# Fri3D_2020_Power.net
KiCad netlist of a schematic drawn in Altium Designer
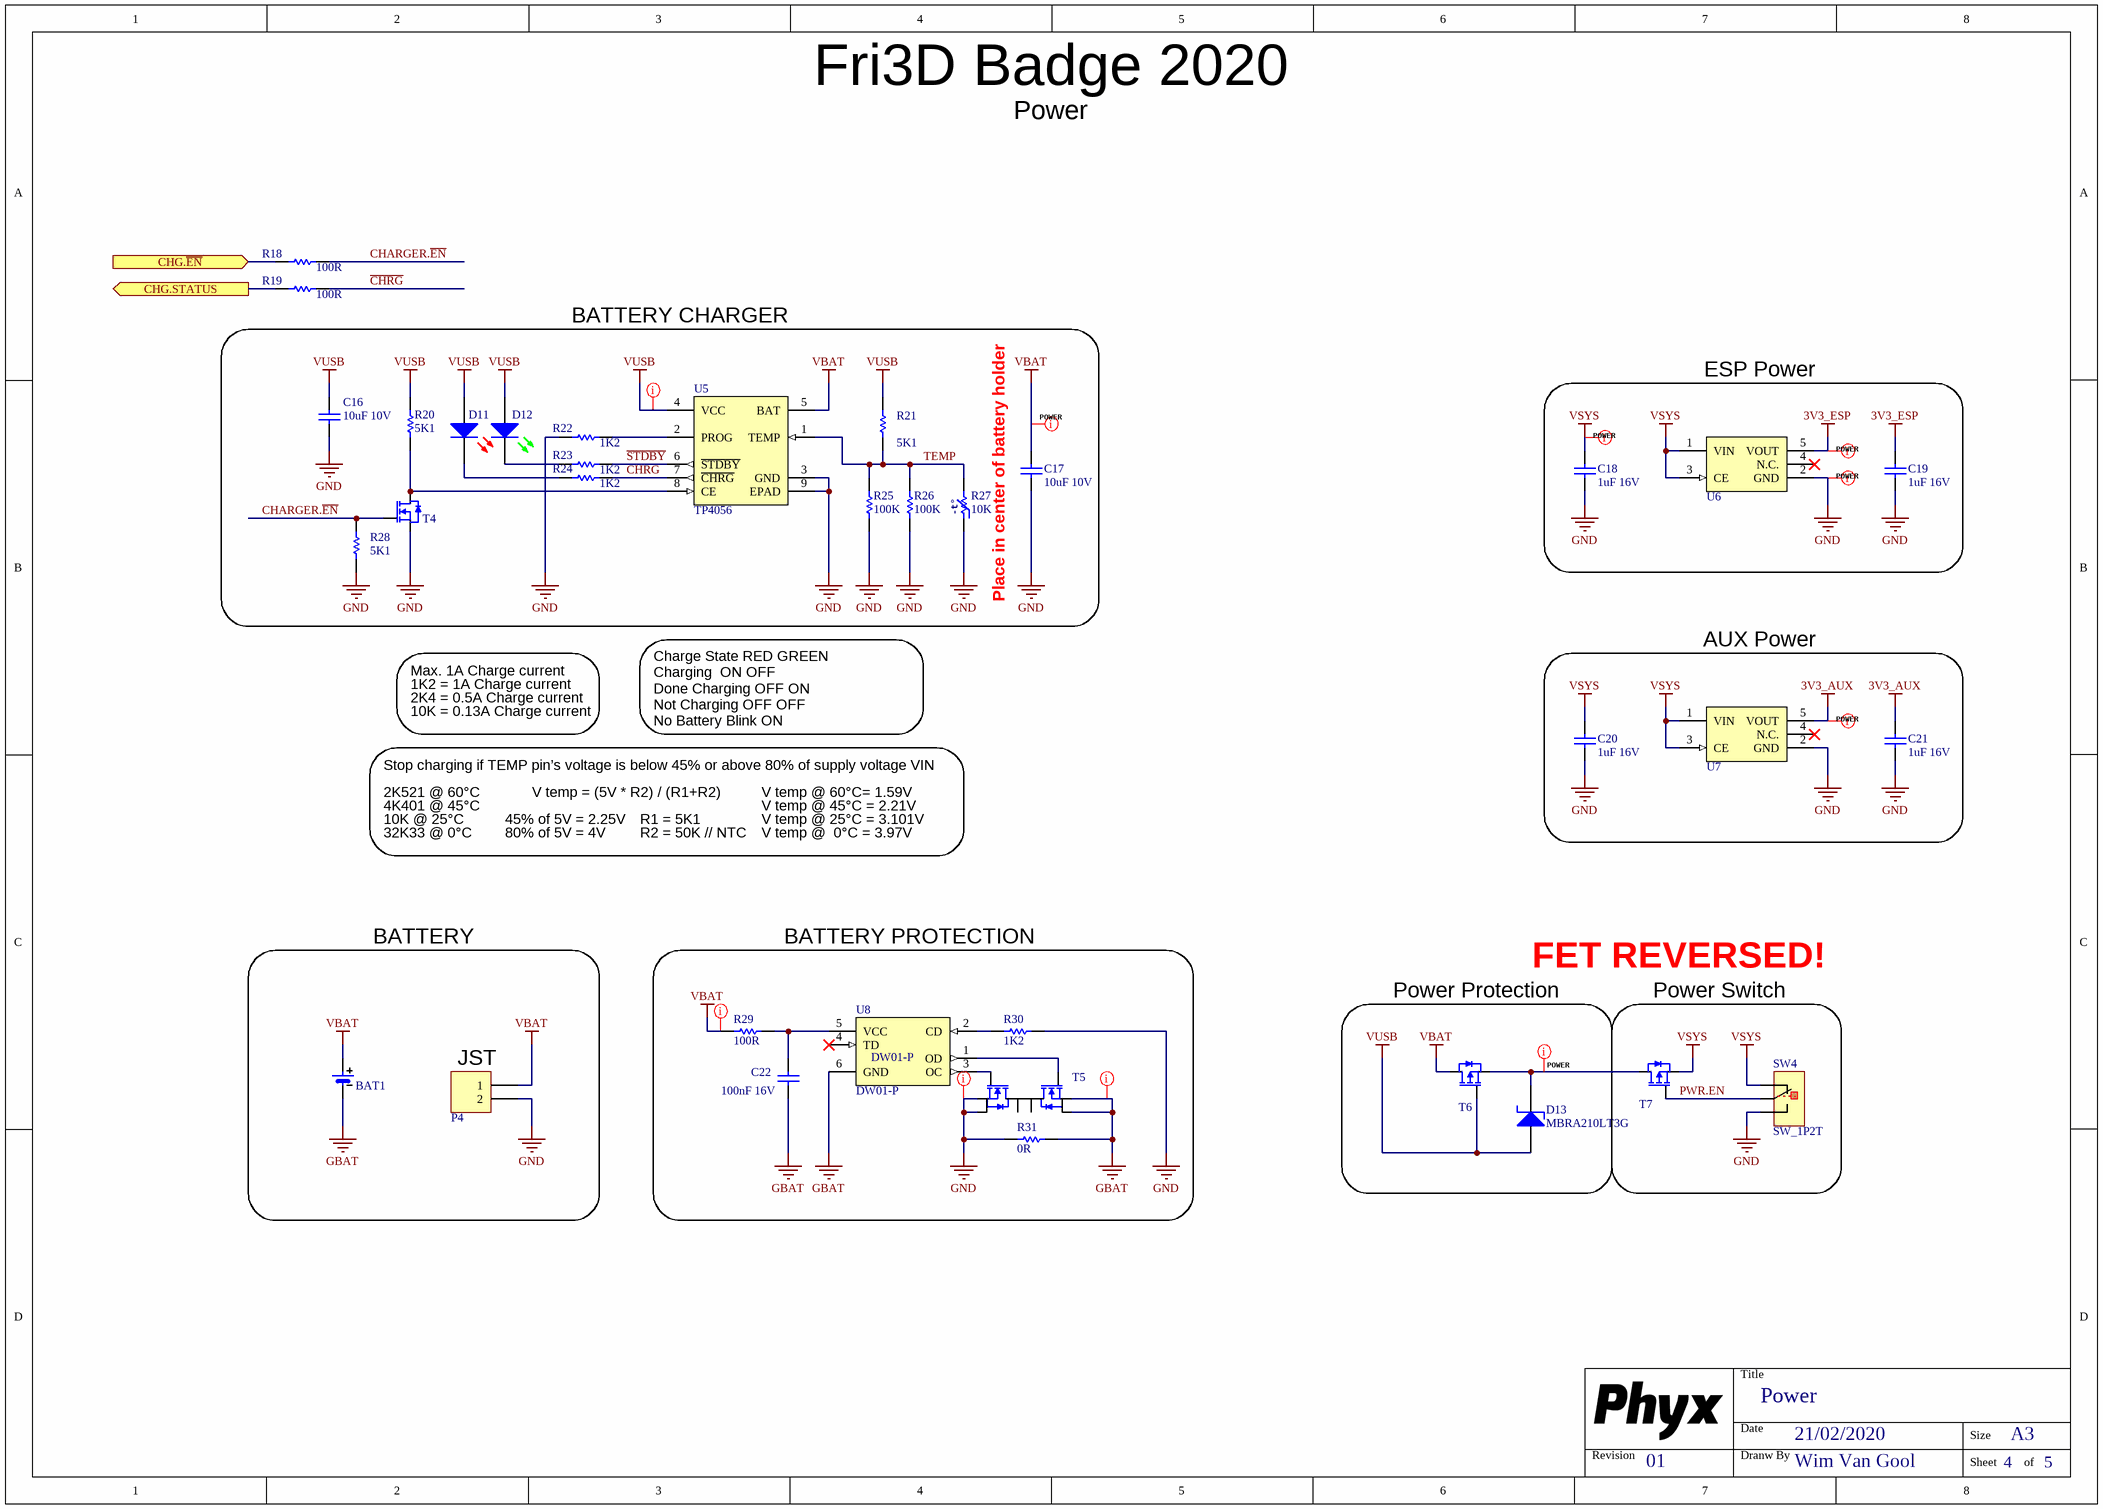
[diagram p0: Fri3D_2020_Power.SchDoc]

(export (version "E")
  (design (tool "Eeschema 10.0.6"))
  (components
    (comp (ref "BAT1")
      (value "18650 Battery holder with spring")
      (footprint "BAT_18650_SPRING")
      (description "=Description")
      (libsource (lib "Phyx_Components") (part "BAT_2"))
    )
    (comp (ref "C16")
      (value "10uF 10V")
      (footprint "C0805_N")
      (description "Capacitor Ceramic")
      (fields (field (name "Comment") "CAP_CERAMIC"))
      (libsource (lib "Phyx_Components") (part "CAP_CERAMIC"))
    )
    (comp (ref "C17")
      (value "10uF 10V")
      (footprint "C0805_N")
      (description "Capacitor Ceramic")
      (fields (field (name "Comment") "CAP_CERAMIC"))
      (libsource (lib "Phyx_Components") (part "CAP_CERAMIC"))
    )
    (comp (ref "C18")
      (value "1uF 16V")
      (footprint "C0603_N")
      (description "Capacitor Ceramic")
      (fields (field (name "Comment") "CAP_CERAMIC"))
      (libsource (lib "Phyx_Components") (part "CAP_CERAMIC"))
    )
    (comp (ref "C19")
      (value "1uF 16V")
      (footprint "C0603_N")
      (description "Capacitor Ceramic")
      (fields (field (name "Comment") "CAP_CERAMIC"))
      (libsource (lib "Phyx_Components") (part "CAP_CERAMIC"))
    )
    (comp (ref "C20")
      (value "1uF 16V")
      (footprint "C0603_N")
      (description "Capacitor Ceramic")
      (fields (field (name "Comment") "CAP_CERAMIC"))
      (libsource (lib "Phyx_Components") (part "CAP_CERAMIC"))
    )
    (comp (ref "C21")
      (value "1uF 16V")
      (footprint "C0603_N")
      (description "Capacitor Ceramic")
      (fields (field (name "Comment") "CAP_CERAMIC"))
      (libsource (lib "Phyx_Components") (part "CAP_CERAMIC"))
    )
    (comp (ref "C22")
      (value "100nF 16V")
      (footprint "C0603_N")
      (description "Capacitor Ceramic")
      (libsource (lib "Phyx_Components") (part "CAP_CERAMIC"))
    )
    (comp (ref "D11")
      (value "Default 0805 Red LED")
      (footprint "LED_0805_RD")
      (description "=Description")
      (libsource (lib "Phyx_Components") (part "LED_RED"))
    )
    (comp (ref "D12")
      (value "Default 0805 Green LED")
      (footprint "LED_0805_GR")
      (description "=Description")
      (libsource (lib "Phyx_Components") (part "LED_GREEN"))
    )
    (comp (ref "D13")
      (value "MBRA210LT3G")
      (footprint "SMA_AC")
      (description "=Description")
      (libsource (lib "Phyx_Components") (part "Schottky_AC"))
    )
    (comp (ref "P4")
      (value "Header 2.0mm Shrouded 2")
      (footprint "WE_620102131822")
      (libsource (lib "Phyx_Components") (part "Header 2"))
    )
    (comp (ref "R18")
      (value "100R")
      (footprint "R0603_N")
      (fields (field (name "Comment") "RESISTOR"))
      (libsource (lib "Phyx_Components") (part "RESISTOR"))
    )
    (comp (ref "R19")
      (value "100R")
      (footprint "R0603_N")
      (fields (field (name "Comment") "RESISTOR"))
      (libsource (lib "Phyx_Components") (part "RESISTOR"))
    )
    (comp (ref "R20")
      (value "5K1")
      (footprint "R0603_N")
      (fields (field (name "Comment") "RESISTOR"))
      (libsource (lib "Phyx_Components") (part "RESISTOR"))
    )
    (comp (ref "R21")
      (value "5K1")
      (footprint "R0603_N")
      (fields (field (name "Comment") "RESISTOR"))
      (libsource (lib "Phyx_Components") (part "RESISTOR"))
    )
    (comp (ref "R22")
      (value "1K2")
      (footprint "R0603_N")
      (fields (field (name "Comment") "RESISTOR"))
      (libsource (lib "Phyx_Components") (part "RESISTOR"))
    )
    (comp (ref "R23")
      (value "1K2")
      (footprint "R0603_N")
      (fields (field (name "Comment") "RESISTOR"))
      (libsource (lib "Phyx_Components") (part "RESISTOR"))
    )
    (comp (ref "R24")
      (value "1K2")
      (footprint "R0603_N")
      (fields (field (name "Comment") "RESISTOR"))
      (libsource (lib "Phyx_Components") (part "RESISTOR"))
    )
    (comp (ref "R25")
      (value "100K")
      (footprint "R0603_N")
      (fields (field (name "Comment") "RESISTOR"))
      (libsource (lib "Phyx_Components") (part "RESISTOR"))
    )
    (comp (ref "R26")
      (value "100K")
      (footprint "R0603_N")
      (fields (field (name "Comment") "RESISTOR"))
      (libsource (lib "Phyx_Components") (part "RESISTOR"))
    )
    (comp (ref "R27")
      (value "10K")
      (footprint "R0402")
      (fields (field (name "Comment") "NTC"))
      (libsource (lib "Phyx_Components") (part "RESISTOR_NTC"))
    )
    (comp (ref "R28")
      (value "5K1")
      (footprint "R0603_N")
      (fields (field (name "Comment") "RESISTOR"))
      (libsource (lib "Phyx_Components") (part "RESISTOR"))
    )
    (comp (ref "R29")
      (value "100R")
      (footprint "R0603_N")
      (fields (field (name "Comment") "RESISTOR"))
      (libsource (lib "Phyx_Components") (part "RESISTOR"))
    )
    (comp (ref "R30")
      (value "1K2")
      (footprint "R0603_N")
      (fields (field (name "Comment") "RESISTOR"))
      (libsource (lib "Phyx_Components") (part "RESISTOR"))
    )
    (comp (ref "R31")
      (value "0R")
      (footprint "R0603_N")
      (libsource (lib "Phyx_Components") (part "RESISTOR"))
    )
    (comp (ref "SW4")
      (value "SW_1P2T")
      (footprint "WE_450404015514")
      (libsource (lib "Phyx_Components") (part "SW_1P2T"))
    )
    (comp (ref "T4")
      (value "0.2A N-Ch MOSFET Vgs 3.2")
      (footprint "SOT23-3")
      (libsource (lib "Phyx_Components") (part "N_MOSFET_GSD"))
    )
    (comp (ref "T5")
      (value "Dual N-Ch MOSFET Common Drain")
      (footprint "TSSOP_8_65P")
      (description "=Description")
      (libsource (lib "Phyx_Components") (part "N_MOSFET_FS8205A"))
    )
    (comp (ref "T6")
      (value "-2.3A -20V P-Ch MOSFET Vgs -1V")
      (footprint "SOT23-3")
      (description "=Description")
      (libsource (lib "Phyx_Components") (part "P_MOSFET_GSD"))
    )
    (comp (ref "T7")
      (value "-2.3A -20V P-Ch MOSFET Vgs -1V")
      (footprint "SOT23-3")
      (description "=Description")
      (libsource (lib "Phyx_Components") (part "P_MOSFET_GSD"))
    )
    (comp (ref "U5")
      (value "TP4056")
      (footprint "SOIC_N_8_TH")
      (description "=Description")
      (fields (field (name "Comment") "Single Cell LiIon charger max 1A"))
      (libsource (lib "Phyx_Components") (part "TP4056"))
    )
    (comp (ref "U6")
      (value "3V3 LDO 700mA 50mV")
      (footprint "SOT23-5")
      (description "=Designator")
      (libsource (lib "Phyx_Components") (part "XC6210_SOT"))
    )
    (comp (ref "U7")
      (value "3V3 LDO 700mA 50mV")
      (footprint "SOT23-5")
      (description "=Designator")
      (libsource (lib "Phyx_Components") (part "XC6210_SOT"))
    )
    (comp (ref "U8")
      (value "DW01-P")
      (footprint "SOT23-6")
      (description "=Description")
      (fields (field (name "Comment") "DW01-P single cell lithium protection"))
      (libsource (lib "Phyx_Components") (part "DW01-P"))
    )
  )
  (nets
    (net (code "1") (name "/CHARGER.~{EN}") (class "Default")
      (node (ref "R18") (pin "2") (pinfunction "2_2") (pintype "passive"))
      (node (ref "R28") (pin "1") (pinfunction "1_1") (pintype "passive"))
      (node (ref "T4") (pin "1") (pinfunction "G_1") (pintype "passive"))
    )
    (net (code "2") (name "/CHG.STATUS") (class "Default")
      (node (ref "R19") (pin "1") (pinfunction "1_1") (pintype "passive"))
    )
    (net (code "3") (name "/CHG.~{EN}") (class "Default")
      (node (ref "R18") (pin "1") (pinfunction "1_1") (pintype "passive"))
    )
    (net (code "4") (name "/PWR.EN") (class "Default")
      (node (ref "SW4") (pin "2") (pinfunction "2_2") (pintype "passive"))
      (node (ref "T7") (pin "1") (pinfunction "G_1") (pintype "passive"))
    )
    (net (code "5") (name "/TEMP") (class "Default")
      (node (ref "R21") (pin "2") (pinfunction "2_2") (pintype "passive"))
      (node (ref "R25") (pin "1") (pinfunction "1_1") (pintype "passive"))
      (node (ref "R26") (pin "1") (pinfunction "1_1") (pintype "passive"))
      (node (ref "R27") (pin "1") (pinfunction "1_1") (pintype "passive"))
      (node (ref "U5") (pin "1") (pinfunction "TEMP_1") (pintype "input"))
    )
    (net (code "6") (name "/~{CHRG}") (class "Default")
      (node (ref "R19") (pin "2") (pinfunction "2_2") (pintype "passive"))
      (node (ref "R24") (pin "2") (pinfunction "2_2") (pintype "passive"))
      (node (ref "U5") (pin "7") (pinfunction "~{CHRG}_7") (pintype "output"))
    )
    (net (code "7") (name "/~{STDBY}") (class "Default")
      (node (ref "R23") (pin "2") (pinfunction "2_2") (pintype "passive"))
      (node (ref "U5") (pin "6") (pinfunction "~{STDBY}_6") (pintype "output"))
    )
    (net (code "8") (name "3V3_AUX") (class "Default")
      (node (ref "C21") (pin "1") (pinfunction "1_1") (pintype "passive"))
      (node (ref "U7") (pin "5") (pinfunction "VOUT_5") (pintype "power_in"))
    )
    (net (code "9") (name "3V3_ESP") (class "Default")
      (node (ref "C19") (pin "1") (pinfunction "1_1") (pintype "passive"))
      (node (ref "U6") (pin "5") (pinfunction "VOUT_5") (pintype "power_in"))
    )
    (net (code "10") (name "GBAT") (class "Default")
      (node (ref "BAT1") (pin "2") (pinfunction "2_2") (pintype "passive"))
      (node (ref "C22") (pin "2") (pinfunction "2_2") (pintype "passive"))
      (node (ref "R31") (pin "1") (pinfunction "1_1") (pintype "passive"))
      (node (ref "T5") (pin "2") (pinfunction "S1_2") (pintype "passive"))
      (node (ref "T5") (pin "3") (pinfunction "S1_3") (pintype "passive"))
      (node (ref "U8") (pin "6") (pinfunction "GND_6") (pintype "power_in"))
    )
    (net (code "11") (name "GND") (class "Default")
      (node (ref "C16") (pin "2") (pinfunction "2_2") (pintype "passive"))
      (node (ref "C17") (pin "2") (pinfunction "2_2") (pintype "passive"))
      (node (ref "C18") (pin "2") (pinfunction "2_2") (pintype "passive"))
      (node (ref "C19") (pin "2") (pinfunction "2_2") (pintype "passive"))
      (node (ref "C20") (pin "2") (pinfunction "2_2") (pintype "passive"))
      (node (ref "C21") (pin "2") (pinfunction "2_2") (pintype "passive"))
      (node (ref "P4") (pin "2") (pinfunction "2_2") (pintype "passive"))
      (node (ref "R22") (pin "2") (pinfunction "2_2") (pintype "passive"))
      (node (ref "R25") (pin "2") (pinfunction "2_2") (pintype "passive"))
      (node (ref "R26") (pin "2") (pinfunction "2_2") (pintype "passive"))
      (node (ref "R27") (pin "2") (pinfunction "2_2") (pintype "passive"))
      (node (ref "R28") (pin "2") (pinfunction "2_2") (pintype "passive"))
      (node (ref "R30") (pin "2") (pinfunction "2_2") (pintype "passive"))
      (node (ref "R31") (pin "2") (pinfunction "2_2") (pintype "passive"))
      (node (ref "SW4") (pin "3") (pinfunction "3_3") (pintype "passive"))
      (node (ref "T4") (pin "2") (pinfunction "S_2") (pintype "passive"))
      (node (ref "T5") (pin "6") (pinfunction "S2_6") (pintype "passive"))
      (node (ref "T5") (pin "7") (pinfunction "S2_7") (pintype "passive"))
      (node (ref "U5") (pin "3") (pinfunction "GND_3") (pintype "power_in"))
      (node (ref "U5") (pin "9") (pinfunction "EPAD_9") (pintype "power_in"))
      (node (ref "U6") (pin "2") (pinfunction "GND_2") (pintype "power_in"))
      (node (ref "U7") (pin "2") (pinfunction "GND_2") (pintype "power_in"))
    )
    (net (code "12") (name "Net-(D11-K)") (class "Default")
      (node (ref "D11") (pin "2") (pinfunction "K_2") (pintype "passive"))
      (node (ref "R24") (pin "1") (pinfunction "1_1") (pintype "passive"))
    )
    (net (code "13") (name "Net-(D12-K)") (class "Default")
      (node (ref "D12") (pin "2") (pinfunction "K_2") (pintype "passive"))
      (node (ref "R23") (pin "1") (pinfunction "1_1") (pintype "passive"))
    )
    (net (code "14") (name "Net-(T4-D)") (class "Default")
      (node (ref "R20") (pin "2") (pinfunction "2_2") (pintype "passive"))
      (node (ref "T4") (pin "3") (pinfunction "D_3") (pintype "passive"))
      (node (ref "U5") (pin "8") (pinfunction "CE_8") (pintype "input"))
    )
    (net (code "15") (name "Net-(T5-G1)") (class "Default")
      (node (ref "T5") (pin "4") (pinfunction "G1_4") (pintype "passive"))
      (node (ref "U8") (pin "1") (pinfunction "OD_1") (pintype "output"))
    )
    (net (code "16") (name "Net-(T5-G2)") (class "Default")
      (node (ref "T5") (pin "5") (pinfunction "G2_5") (pintype "passive"))
      (node (ref "U8") (pin "3") (pinfunction "OC_3") (pintype "output"))
    )
    (net (code "17") (name "Net-(T6-S)") (class "Default")
      (node (ref "D13") (pin "C") (pinfunction "C_C") (pintype "passive"))
      (node (ref "T6") (pin "2") (pinfunction "S_2") (pintype "passive"))
      (node (ref "T7") (pin "3") (pinfunction "D_3") (pintype "passive"))
    )
    (net (code "18") (name "Net-(U5-PROG)") (class "Default")
      (node (ref "R22") (pin "1") (pinfunction "1_1") (pintype "passive"))
      (node (ref "U5") (pin "2") (pinfunction "PROG_2") (pintype "passive"))
    )
    (net (code "19") (name "Net-(U8-CD)") (class "Default")
      (node (ref "R30") (pin "1") (pinfunction "1_1") (pintype "passive"))
      (node (ref "U8") (pin "2") (pinfunction "CD_2") (pintype "input"))
    )
    (net (code "20") (name "Net-(U8-VCC)") (class "Default")
      (node (ref "C22") (pin "1") (pinfunction "1_1") (pintype "passive"))
      (node (ref "R29") (pin "2") (pinfunction "2_2") (pintype "passive"))
      (node (ref "U8") (pin "5") (pinfunction "VCC_5") (pintype "power_in"))
    )
    (net (code "21") (name "VBAT") (class "Default")
      (node (ref "BAT1") (pin "1") (pinfunction "1_1") (pintype "passive"))
      (node (ref "C17") (pin "1") (pinfunction "1_1") (pintype "passive"))
      (node (ref "P4") (pin "1") (pinfunction "1_1") (pintype "passive"))
      (node (ref "R29") (pin "1") (pinfunction "1_1") (pintype "passive"))
      (node (ref "T6") (pin "3") (pinfunction "D_3") (pintype "passive"))
      (node (ref "U5") (pin "5") (pinfunction "BAT_5") (pintype "power_in"))
    )
    (net (code "22") (name "VSYS") (class "Default")
      (node (ref "C18") (pin "1") (pinfunction "1_1") (pintype "passive"))
      (node (ref "C20") (pin "1") (pinfunction "1_1") (pintype "passive"))
      (node (ref "SW4") (pin "1") (pinfunction "1_1") (pintype "passive"))
      (node (ref "T7") (pin "2") (pinfunction "S_2") (pintype "passive"))
      (node (ref "U6") (pin "1") (pinfunction "VIN_1") (pintype "power_in"))
      (node (ref "U6") (pin "3") (pinfunction "CE_3") (pintype "input"))
      (node (ref "U7") (pin "1") (pinfunction "VIN_1") (pintype "power_in"))
      (node (ref "U7") (pin "3") (pinfunction "CE_3") (pintype "input"))
    )
    (net (code "23") (name "VUSB") (class "Default")
      (node (ref "C16") (pin "1") (pinfunction "1_1") (pintype "passive"))
      (node (ref "D11") (pin "1") (pinfunction "A_1") (pintype "passive"))
      (node (ref "D12") (pin "1") (pinfunction "A_1") (pintype "passive"))
      (node (ref "D13") (pin "A") (pinfunction "A_A") (pintype "passive"))
      (node (ref "R20") (pin "1") (pinfunction "1_1") (pintype "passive"))
      (node (ref "R21") (pin "1") (pinfunction "1_1") (pintype "passive"))
      (node (ref "T6") (pin "1") (pinfunction "G_1") (pintype "passive"))
      (node (ref "U5") (pin "4") (pinfunction "VCC_4") (pintype "power_in"))
    )
    (net (code "24") (name "unconnected-(T5-D1-Pad1)") (class "Default")
      (node (ref "T5") (pin "1") (pinfunction "D1_1") (pintype "passive"))
    )
    (net (code "25") (name "unconnected-(T5-D2-Pad8)") (class "Default")
      (node (ref "T5") (pin "8") (pinfunction "D2_8") (pintype "passive"))
    )
    (net (code "26") (name "unconnected-(U6-N.C.-Pad4)") (class "Default")
      (node (ref "U6") (pin "4") (pinfunction "N.C._4") (pintype "passive+no_connect"))
    )
    (net (code "27") (name "unconnected-(U7-N.C.-Pad4)") (class "Default")
      (node (ref "U7") (pin "4") (pinfunction "N.C._4") (pintype "passive+no_connect"))
    )
    (net (code "28") (name "unconnected-(U8-TD-Pad4)") (class "Default")
      (node (ref "U8") (pin "4") (pinfunction "TD_4") (pintype "input+no_connect"))
    )
  )
)
